# UsbKerb.net
KiCad netlist of a schematic drawn in EAGLE
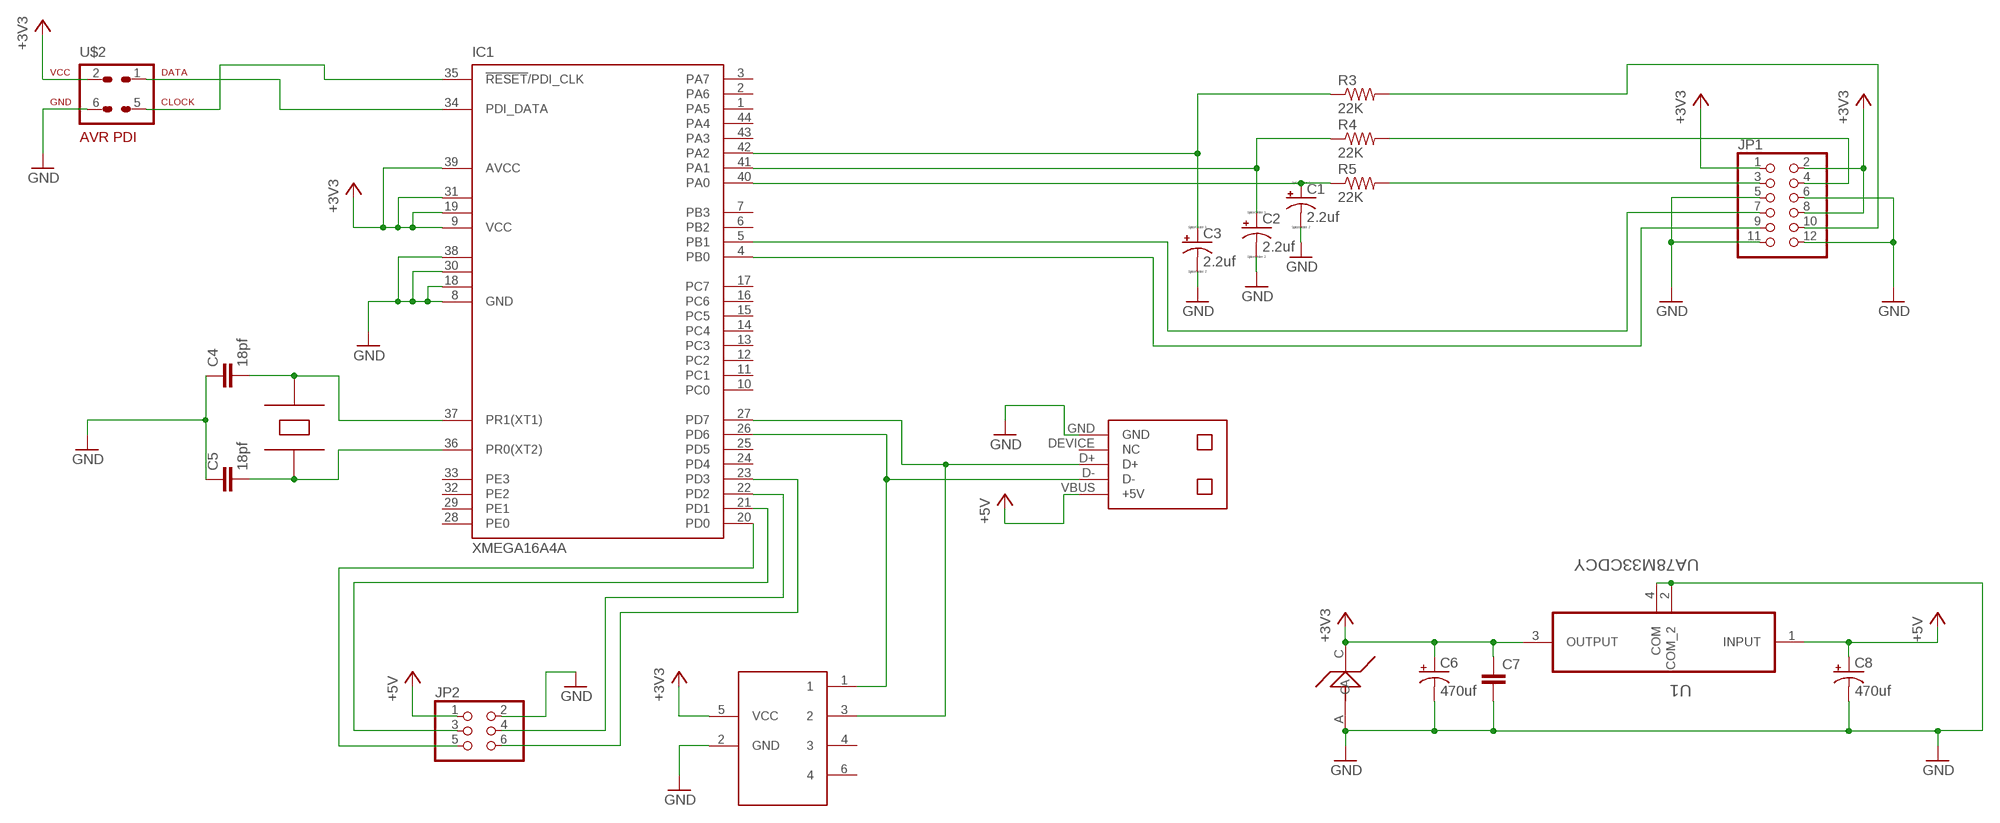
[diagram p0: schematic, sheet 1]

(export (version "E")
  (design (tool "Eeschema 10.0.6"))
  (components
    (comp (ref "C1")
      (value "2.2uf")
      (footprint "eagle-import:PANASONIC_B")
      (libsource (lib "eagle-import") (part "resistor_CPOL-USB"))
    )
    (comp (ref "C2")
      (value "2.2uf")
      (footprint "eagle-import:PANASONIC_B")
      (libsource (lib "eagle-import") (part "resistor_CPOL-USB"))
    )
    (comp (ref "C3")
      (value "2.2uf")
      (footprint "eagle-import:PANASONIC_B")
      (libsource (lib "eagle-import") (part "resistor_CPOL-USB"))
    )
    (comp (ref "C4")
      (value "18pf")
      (footprint "eagle-import:C0805K")
      (libsource (lib "eagle-import") (part "C-EUC0805K"))
    )
    (comp (ref "C5")
      (value "18pf")
      (footprint "eagle-import:C0805K")
      (libsource (lib "eagle-import") (part "C-EUC0805K"))
    )
    (comp (ref "C6")
      (value "470uf")
      (footprint "eagle-import:PANASONIC_G")
      (libsource (lib "eagle-import") (part "CPOL-USG"))
    )
    (comp (ref "C7")
      (value "C-EUC1206K")
      (footprint "eagle-import:C1206K")
      (libsource (lib "eagle-import") (part "resistor_C-EUC1206K"))
    )
    (comp (ref "C8")
      (value "470uf")
      (footprint "eagle-import:PANASONIC_G")
      (libsource (lib "eagle-import") (part "CPOL-USG"))
    )
    (comp (ref "IC1")
      (value "XMEGA16A4A")
      (footprint "eagle-import:TQFP44")
      (libsource (lib "eagle-import") (part "XMEGA16A4A"))
    )
    (comp (ref "JP1")
      (value "PINHD-2X6")
      (footprint "eagle-import:2X06")
      (libsource (lib "eagle-import") (part "PINHD-2X6"))
    )
    (comp (ref "JP2")
      (value "PINHD-2X3")
      (footprint "eagle-import:2X03")
      (libsource (lib "eagle-import") (part "PINHD-2X3"))
    )
    (comp (ref "R3")
      (value "22K")
      (footprint "eagle-import:R0805W")
      (libsource (lib "eagle-import") (part "R-US_R0805W"))
    )
    (comp (ref "R4")
      (value "22K")
      (footprint "eagle-import:R0805W")
      (libsource (lib "eagle-import") (part "R-US_R0805W"))
    )
    (comp (ref "R5")
      (value "22K")
      (footprint "eagle-import:R0805W")
      (libsource (lib "eagle-import") (part "R-US_R0805W"))
    )
    (comp (ref "U$1")
      (value "USB-MINI")
      (footprint "eagle-import:USB-MINI")
      (libsource (lib "eagle-import") (part "USB-MINI"))
    )
    (comp (ref "U$2")
      (value "AVR-PDIVERT")
      (footprint "eagle-import:AVR-ISP-6")
      (libsource (lib "eagle-import") (part "AVR-PDIVERT"))
    )
    (comp (ref "U$3")
      (value "TVS")
      (footprint "eagle-import:DO214AC")
      (libsource (lib "eagle-import") (part "TVS"))
    )
    (comp (ref "U$4")
      (value "12MHZ")
      (footprint "eagle-import:12MHZ")
      (libsource (lib "eagle-import") (part "12MHZ"))
    )
    (comp (ref "U1")
      (value "UA78M33CDCY")
      (footprint "eagle-import:SOT230P700X180-4N")
      (libsource (lib "eagle-import") (part "UA78M33CDCY"))
    )
    (comp (ref "U2")
      (value "3.3TVS")
      (footprint "eagle-import:SOT23-6L")
      (libsource (lib "eagle-import") (part "3.3TVS"))
    )
  )
  (nets
    (net (code "1") (name "+3V3") (class "Default")
      (node (ref "C6") (pin "+") (pinfunction "+_+") (pintype "passive"))
      (node (ref "C7") (pin "1") (pinfunction "1_1") (pintype "passive"))
      (node (ref "IC1") (pin "19") (pinfunction "VCC1_19") (pintype "power_in"))
      (node (ref "IC1") (pin "31") (pinfunction "VCC2_31") (pintype "power_in"))
      (node (ref "IC1") (pin "39") (pinfunction "AVCC_39") (pintype "power_in"))
      (node (ref "IC1") (pin "9") (pinfunction "VCC_9") (pintype "power_in"))
      (node (ref "JP1") (pin "1") (pinfunction "1_1") (pintype "passive"))
      (node (ref "JP1") (pin "2") (pinfunction "2_2") (pintype "passive"))
      (node (ref "JP1") (pin "8") (pinfunction "8_8") (pintype "passive"))
      (node (ref "U$2") (pin "2") (pinfunction "2_2") (pintype "passive"))
      (node (ref "U$3") (pin "C") (pinfunction "C_C") (pintype "bidirectional"))
      (node (ref "U1") (pin "3") (pinfunction "OUTPUT_3") (pintype "output"))
      (node (ref "U2") (pin "5") (pinfunction "VCC_5") (pintype "bidirectional"))
    )
    (net (code "2") (name "+5V") (class "Default")
      (node (ref "C8") (pin "+") (pinfunction "+_+") (pintype "passive"))
      (node (ref "JP2") (pin "1") (pinfunction "1_1") (pintype "passive"))
      (node (ref "U$1") (pin "VBUS") (pinfunction "+5V_VBUS") (pintype "bidirectional"))
      (node (ref "U1") (pin "1") (pinfunction "INPUT_1") (pintype "input"))
    )
    (net (code "3") (name "GND") (class "Default")
      (node (ref "C1") (pin "-") (pinfunction "-_-") (pintype "passive"))
      (node (ref "C2") (pin "-") (pinfunction "-_-") (pintype "passive"))
      (node (ref "C3") (pin "-") (pinfunction "-_-") (pintype "passive"))
      (node (ref "C4") (pin "1") (pinfunction "1_1") (pintype "passive"))
      (node (ref "C5") (pin "1") (pinfunction "1_1") (pintype "passive"))
      (node (ref "C6") (pin "-") (pinfunction "-_-") (pintype "passive"))
      (node (ref "C7") (pin "2") (pinfunction "2_2") (pintype "passive"))
      (node (ref "C8") (pin "-") (pinfunction "-_-") (pintype "passive"))
      (node (ref "IC1") (pin "18") (pinfunction "GND1_18") (pintype "power_in"))
      (node (ref "IC1") (pin "30") (pinfunction "GND2_30") (pintype "power_in"))
      (node (ref "IC1") (pin "38") (pinfunction "GND3_38") (pintype "power_in"))
      (node (ref "IC1") (pin "8") (pinfunction "GND_8") (pintype "power_in"))
      (node (ref "JP1") (pin "11") (pinfunction "11_11") (pintype "passive"))
      (node (ref "JP1") (pin "12") (pinfunction "12_12") (pintype "passive"))
      (node (ref "JP1") (pin "5") (pinfunction "5_5") (pintype "passive"))
      (node (ref "JP1") (pin "6") (pinfunction "6_6") (pintype "passive"))
      (node (ref "JP2") (pin "2") (pinfunction "2_2") (pintype "passive"))
      (node (ref "U$1") (pin "GND") (pinfunction "GND_GND") (pintype "bidirectional"))
      (node (ref "U$2") (pin "6") (pinfunction "6_6") (pintype "passive"))
      (node (ref "U$3") (pin "A") (pinfunction "A_A") (pintype "bidirectional"))
      (node (ref "U1") (pin "2") (pinfunction "COM_2_2") (pintype "passive"))
      (node (ref "U1") (pin "4") (pinfunction "COM_4") (pintype "passive"))
      (node (ref "U2") (pin "2") (pinfunction "GND_2") (pintype "bidirectional"))
    )
    (net (code "4") (name "Net-(IC1-PA0)") (class "Default")
      (node (ref "C1") (pin "+") (pinfunction "+_+") (pintype "passive"))
      (node (ref "IC1") (pin "40") (pinfunction "PA0_40") (pintype "bidirectional"))
      (node (ref "R5") (pin "1") (pinfunction "1_1") (pintype "passive"))
    )
    (net (code "5") (name "Net-(IC1-PA1)") (class "Default")
      (node (ref "C2") (pin "+") (pinfunction "+_+") (pintype "passive"))
      (node (ref "IC1") (pin "41") (pinfunction "PA1_41") (pintype "bidirectional"))
      (node (ref "R4") (pin "1") (pinfunction "1_1") (pintype "passive"))
    )
    (net (code "6") (name "Net-(IC1-PA2)") (class "Default")
      (node (ref "C3") (pin "+") (pinfunction "+_+") (pintype "passive"))
      (node (ref "IC1") (pin "42") (pinfunction "PA2_42") (pintype "bidirectional"))
      (node (ref "R3") (pin "1") (pinfunction "1_1") (pintype "passive"))
    )
    (net (code "7") (name "Net-(IC1-PB0)") (class "Default")
      (node (ref "IC1") (pin "4") (pinfunction "PB0_4") (pintype "bidirectional"))
      (node (ref "JP1") (pin "9") (pinfunction "9_9") (pintype "passive"))
    )
    (net (code "8") (name "Net-(IC1-PB1)") (class "Default")
      (node (ref "IC1") (pin "5") (pinfunction "PB1_5") (pintype "bidirectional"))
      (node (ref "JP1") (pin "7") (pinfunction "7_7") (pintype "passive"))
    )
    (net (code "9") (name "Net-(IC1-PD0)") (class "Default")
      (node (ref "IC1") (pin "20") (pinfunction "PD0_20") (pintype "bidirectional"))
      (node (ref "JP2") (pin "5") (pinfunction "5_5") (pintype "passive"))
    )
    (net (code "10") (name "Net-(IC1-PD1)") (class "Default")
      (node (ref "IC1") (pin "21") (pinfunction "PD1_21") (pintype "bidirectional"))
      (node (ref "JP2") (pin "3") (pinfunction "3_3") (pintype "passive"))
    )
    (net (code "11") (name "Net-(IC1-PD2)") (class "Default")
      (node (ref "IC1") (pin "22") (pinfunction "PD2_22") (pintype "bidirectional"))
      (node (ref "JP2") (pin "4") (pinfunction "4_4") (pintype "passive"))
    )
    (net (code "12") (name "Net-(IC1-PD3)") (class "Default")
      (node (ref "IC1") (pin "23") (pinfunction "PD3_23") (pintype "bidirectional"))
      (node (ref "JP2") (pin "6") (pinfunction "6_6") (pintype "passive"))
    )
    (net (code "13") (name "Net-(IC1-PD6)") (class "Default")
      (node (ref "IC1") (pin "26") (pinfunction "PD6_26") (pintype "bidirectional"))
      (node (ref "U$1") (pin "D-") (pinfunction "D-_D-") (pintype "bidirectional"))
      (node (ref "U2") (pin "1") (pinfunction "1_1") (pintype "bidirectional"))
    )
    (net (code "14") (name "Net-(IC1-PD7)") (class "Default")
      (node (ref "IC1") (pin "27") (pinfunction "PD7_27") (pintype "bidirectional"))
      (node (ref "U$1") (pin "D+") (pinfunction "D+_D+") (pintype "bidirectional"))
      (node (ref "U2") (pin "3") (pinfunction "2_3") (pintype "bidirectional"))
    )
    (net (code "15") (name "Net-(IC1-PDI_DATA)") (class "Default")
      (node (ref "IC1") (pin "34") (pinfunction "PDI_DATA_34") (pintype "bidirectional"))
      (node (ref "U$2") (pin "1") (pinfunction "1_1") (pintype "passive"))
    )
    (net (code "16") (name "Net-(IC1-PR0(XT2))") (class "Default")
      (node (ref "C5") (pin "2") (pinfunction "2_2") (pintype "passive"))
      (node (ref "IC1") (pin "36") (pinfunction "PR0(XT2)_36") (pintype "bidirectional"))
      (node (ref "U$4") (pin "P$2") (pinfunction "P$2_P$2") (pintype "bidirectional"))
    )
    (net (code "17") (name "Net-(IC1-PR1(XT1))") (class "Default")
      (node (ref "C4") (pin "2") (pinfunction "2_2") (pintype "passive"))
      (node (ref "IC1") (pin "37") (pinfunction "PR1(XT1)_37") (pintype "bidirectional"))
      (node (ref "U$4") (pin "P$1") (pinfunction "P$1_P$1") (pintype "bidirectional"))
    )
    (net (code "18") (name "Net-(IC1-~{RESET}{slash}PDI_CLK)") (class "Default")
      (node (ref "IC1") (pin "35") (pinfunction "~{RESET}/PDI_CLK_35") (pintype "bidirectional"))
      (node (ref "U$2") (pin "5") (pinfunction "5_5") (pintype "passive"))
    )
    (net (code "19") (name "Net-(JP1-Pad3)") (class "Default")
      (node (ref "JP1") (pin "3") (pinfunction "3_3") (pintype "passive"))
      (node (ref "R5") (pin "2") (pinfunction "2_2") (pintype "passive"))
    )
    (net (code "20") (name "Net-(JP1-Pad4)") (class "Default")
      (node (ref "JP1") (pin "4") (pinfunction "4_4") (pintype "passive"))
      (node (ref "R4") (pin "2") (pinfunction "2_2") (pintype "passive"))
    )
    (net (code "21") (name "Net-(JP1-Pad10)") (class "Default")
      (node (ref "JP1") (pin "10") (pinfunction "10_10") (pintype "passive"))
      (node (ref "R3") (pin "2") (pinfunction "2_2") (pintype "passive"))
    )
    (net (code "22") (name "unconnected-(IC1-PA3-Pad43)") (class "Default")
      (node (ref "IC1") (pin "43") (pinfunction "PA3_43") (pintype "bidirectional"))
    )
    (net (code "23") (name "unconnected-(IC1-PA4-Pad44)") (class "Default")
      (node (ref "IC1") (pin "44") (pinfunction "PA4_44") (pintype "bidirectional"))
    )
    (net (code "24") (name "unconnected-(IC1-PA5-Pad1)") (class "Default")
      (node (ref "IC1") (pin "1") (pinfunction "PA5_1") (pintype "bidirectional"))
    )
    (net (code "25") (name "unconnected-(IC1-PA6-Pad2)") (class "Default")
      (node (ref "IC1") (pin "2") (pinfunction "PA6_2") (pintype "bidirectional"))
    )
    (net (code "26") (name "unconnected-(IC1-PA7-Pad3)") (class "Default")
      (node (ref "IC1") (pin "3") (pinfunction "PA7_3") (pintype "bidirectional"))
    )
    (net (code "27") (name "unconnected-(IC1-PB2-Pad6)") (class "Default")
      (node (ref "IC1") (pin "6") (pinfunction "PB2_6") (pintype "bidirectional"))
    )
    (net (code "28") (name "unconnected-(IC1-PB3-Pad7)") (class "Default")
      (node (ref "IC1") (pin "7") (pinfunction "PB3_7") (pintype "bidirectional"))
    )
    (net (code "29") (name "unconnected-(IC1-PC0-Pad10)") (class "Default")
      (node (ref "IC1") (pin "10") (pinfunction "PC0_10") (pintype "bidirectional"))
    )
    (net (code "30") (name "unconnected-(IC1-PC1-Pad11)") (class "Default")
      (node (ref "IC1") (pin "11") (pinfunction "PC1_11") (pintype "bidirectional"))
    )
    (net (code "31") (name "unconnected-(IC1-PC2-Pad12)") (class "Default")
      (node (ref "IC1") (pin "12") (pinfunction "PC2_12") (pintype "bidirectional"))
    )
    (net (code "32") (name "unconnected-(IC1-PC3-Pad13)") (class "Default")
      (node (ref "IC1") (pin "13") (pinfunction "PC3_13") (pintype "bidirectional"))
    )
    (net (code "33") (name "unconnected-(IC1-PC4-Pad14)") (class "Default")
      (node (ref "IC1") (pin "14") (pinfunction "PC4_14") (pintype "bidirectional"))
    )
    (net (code "34") (name "unconnected-(IC1-PC5-Pad15)") (class "Default")
      (node (ref "IC1") (pin "15") (pinfunction "PC5_15") (pintype "bidirectional"))
    )
    (net (code "35") (name "unconnected-(IC1-PC6-Pad16)") (class "Default")
      (node (ref "IC1") (pin "16") (pinfunction "PC6_16") (pintype "bidirectional"))
    )
    (net (code "36") (name "unconnected-(IC1-PC7-Pad17)") (class "Default")
      (node (ref "IC1") (pin "17") (pinfunction "PC7_17") (pintype "bidirectional"))
    )
    (net (code "37") (name "unconnected-(IC1-PD4-Pad24)") (class "Default")
      (node (ref "IC1") (pin "24") (pinfunction "PD4_24") (pintype "bidirectional"))
    )
    (net (code "38") (name "unconnected-(IC1-PD5-Pad25)") (class "Default")
      (node (ref "IC1") (pin "25") (pinfunction "PD5_25") (pintype "bidirectional"))
    )
    (net (code "39") (name "unconnected-(IC1-PE0-Pad28)") (class "Default")
      (node (ref "IC1") (pin "28") (pinfunction "PE0_28") (pintype "bidirectional"))
    )
    (net (code "40") (name "unconnected-(IC1-PE1-Pad29)") (class "Default")
      (node (ref "IC1") (pin "29") (pinfunction "PE1_29") (pintype "bidirectional"))
    )
    (net (code "41") (name "unconnected-(IC1-PE2-Pad32)") (class "Default")
      (node (ref "IC1") (pin "32") (pinfunction "PE2_32") (pintype "bidirectional"))
    )
    (net (code "42") (name "unconnected-(IC1-PE3-Pad33)") (class "Default")
      (node (ref "IC1") (pin "33") (pinfunction "PE3_33") (pintype "bidirectional"))
    )
    (net (code "43") (name "unconnected-(U$1-NC-PadDEVICE)") (class "Default")
      (node (ref "U$1") (pin "DEVICE") (pinfunction "NC_DEVICE") (pintype "bidirectional"))
    )
    (net (code "44") (name "unconnected-(U2-3-Pad4)") (class "Default")
      (node (ref "U2") (pin "4") (pinfunction "3_4") (pintype "bidirectional"))
    )
    (net (code "45") (name "unconnected-(U2-4-Pad6)") (class "Default")
      (node (ref "U2") (pin "6") (pinfunction "4_6") (pintype "bidirectional"))
    )
  )
)
